# power.net
KiCad netlist of a schematic drawn in Altium Designer
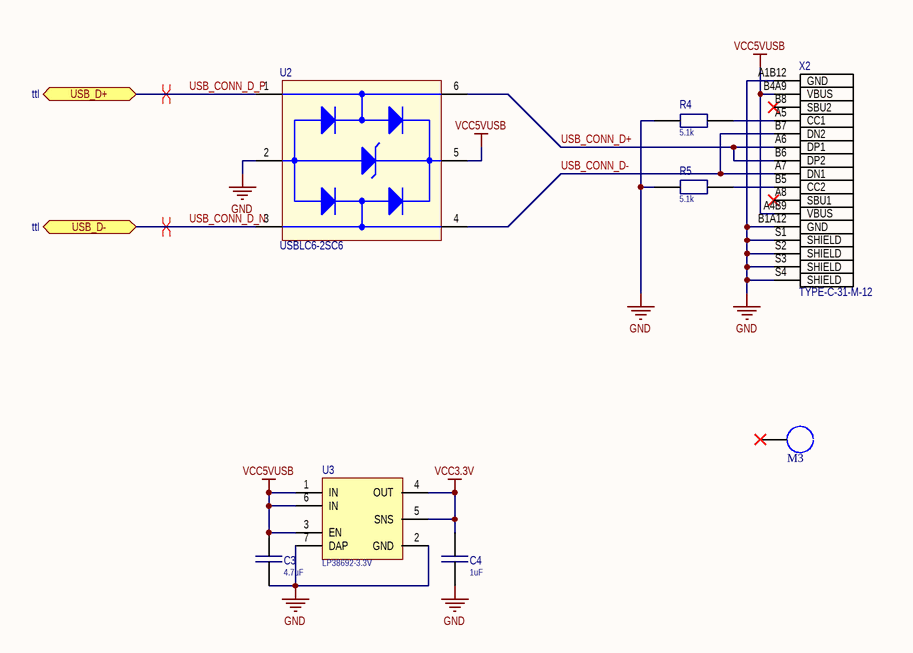
[diagram p0: power.SchDoc]

(export (version "E")
  (design (tool "Eeschema 10.0.6"))
  (components
    (comp (ref "*1") (value "M3") (footprint "M3") (libsource (lib "connectors_socets") (part "M3")))
    (comp (ref "C3")
      (value "4.7uF")
      (footprint "C_0603")
      (description "Capacitor")
      (fields (field (name "PART NUMBER") "CC0603KRX5R6BB475"))
      (libsource (lib "capacitors") (part "CAP_SMD"))
    )
    (comp (ref "C4")
      (value "1uF")
      (footprint "C_0603")
      (description "Capacitor")
      (fields (field (name "PART NUMBER") "CC0603ZRY5V7BB105"))
      (libsource (lib "capacitors") (part "CAP_SMD"))
    )
    (comp (ref "R4")
      (value "5.1k")
      (footprint "R_0603")
      (description "Resistor")
      (fields (field (name "PART NUMBER") "RC0603FR-075K1L"))
      (libsource (lib "resistors") (part "RES_SMD"))
    )
    (comp (ref "R5")
      (value "5.1k")
      (footprint "R_0603")
      (description "Resistor")
      (fields (field (name "PART NUMBER") "RC0603FR-075K1L"))
      (libsource (lib "resistors") (part "RES_SMD"))
    )
    (comp (ref "U2")
      (value "USBLC6-2SC6")
      (footprint "diode:SOT95P280X145-6N")
      (description "17V Clamp 5A (8/20Âµs) Ipp Tvs Diode Surface Mount SOT-23-6")
      (fields (field (name "MF") "STMicroelectronics"))
      (libsource (lib "diode") (part "USBLC6-2SC6"))
    )
    (comp (ref "U3")
      (value "LP38692-3.3V")
      (footprint "WSON-6")
      (description "LP38690, LP38692 1-A LDO CMOS Linear Regulators  Stable with Ceramic Output Capacitors")
      (libsource (lib "AX_Altium_v2.3") (part "LP38692"))
    )
    (comp (ref "X2")
      (value "TYPE-C-31-M-12")
      (footprint "connectors_socets:HRO_TYPE-C-31-M-12")
      (description "USB Connectors 24 Receptacle 1 8.94*7.3mm RoHS")
      (libsource (lib "connectors_socets") (part "TYPE-C-31-M-12"))
    )
  )
  (nets
    (net (code "1") (name "/USB_CONN_D+") (class "Default")
      (node (ref "U2") (pin "6") (pinfunction "I/O1_OUT_6") (pintype "passive"))
      (node (ref "X2") (pin "A6") (pinfunction "DP1_A6") (pintype "passive"))
      (node (ref "X2") (pin "B6") (pinfunction "DP2_B6") (pintype "passive"))
    )
    (net (code "2") (name "/USB_CONN_D-") (class "Default")
      (node (ref "U2") (pin "4") (pinfunction "I/O2_OUT_4") (pintype "passive"))
      (node (ref "X2") (pin "A7") (pinfunction "DN1_A7") (pintype "passive"))
      (node (ref "X2") (pin "B7") (pinfunction "DN2_B7") (pintype "passive"))
    )
    (net (code "3") (name "/USB_CONN_D_N") (class "Default")
      (node (ref "U2") (pin "3") (pinfunction "I/O2_IN_3") (pintype "passive"))
    )
    (net (code "4") (name "/USB_CONN_D_P") (class "Default")
      (node (ref "U2") (pin "1") (pinfunction "I/O1_IN_1") (pintype "passive"))
    )
    (net (code "5") (name "GND") (class "Default")
      (node (ref "C3") (pin "1") (pinfunction "1_1") (pintype "passive"))
      (node (ref "C4") (pin "1") (pinfunction "1_1") (pintype "passive"))
      (node (ref "R4") (pin "1") (pinfunction "1_1") (pintype "passive"))
      (node (ref "R5") (pin "1") (pinfunction "1_1") (pintype "passive"))
      (node (ref "U2") (pin "2") (pinfunction "GND_2") (pintype "passive"))
      (node (ref "U3") (pin "2") (pinfunction "GND_2") (pintype "passive"))
      (node (ref "U3") (pin "7") (pinfunction "DAP_7") (pintype "passive"))
      (node (ref "X2") (pin "A1B12") (pinfunction "GND_A1B12") (pintype "passive"))
      (node (ref "X2") (pin "B1A12") (pinfunction "GND_B1A12") (pintype "passive"))
      (node (ref "X2") (pin "S1") (pinfunction "SHIELD_S1") (pintype "passive"))
      (node (ref "X2") (pin "S2") (pinfunction "SHIELD_S2") (pintype "passive"))
      (node (ref "X2") (pin "S3") (pinfunction "SHIELD_S3") (pintype "passive"))
      (node (ref "X2") (pin "S4") (pinfunction "SHIELD_S4") (pintype "passive"))
    )
    (net (code "6") (name "Net-(X2-CC1)") (class "Default")
      (node (ref "R4") (pin "2") (pinfunction "2_2") (pintype "passive"))
      (node (ref "X2") (pin "A5") (pinfunction "CC1_A5") (pintype "passive"))
    )
    (net (code "7") (name "Net-(X2-CC2)") (class "Default")
      (node (ref "R5") (pin "2") (pinfunction "2_2") (pintype "passive"))
      (node (ref "X2") (pin "B5") (pinfunction "CC2_B5") (pintype "passive"))
    )
    (net (code "8") (name "VCC3.3V") (class "Default")
      (node (ref "C4") (pin "2") (pinfunction "2_2") (pintype "passive"))
      (node (ref "U3") (pin "4") (pinfunction "OUT_4") (pintype "passive"))
      (node (ref "U3") (pin "5") (pinfunction "SNS_5") (pintype "passive"))
    )
    (net (code "9") (name "VCC5VUSB") (class "Default")
      (node (ref "C3") (pin "2") (pinfunction "2_2") (pintype "passive"))
      (node (ref "U2") (pin "5") (pinfunction "VBUS_5") (pintype "passive"))
      (node (ref "U3") (pin "1") (pinfunction "IN_1") (pintype "passive"))
      (node (ref "U3") (pin "3") (pinfunction "EN_3") (pintype "passive"))
      (node (ref "U3") (pin "6") (pinfunction "IN_6") (pintype "passive"))
      (node (ref "X2") (pin "A4B9") (pinfunction "VBUS_A4B9") (pintype "passive"))
      (node (ref "X2") (pin "B4A9") (pinfunction "VBUS_B4A9") (pintype "passive"))
    )
    (net (code "10") (name "unconnected-(*1-Pad1)") (class "Default")
      (node (ref "*1") (pin "1") (pinfunction "1_1") (pintype "passive+no_connect"))
    )
    (net (code "11") (name "unconnected-(X2-SBU1-PadA8)") (class "Default")
      (node (ref "X2") (pin "A8") (pinfunction "SBU1_A8") (pintype "passive+no_connect"))
    )
    (net (code "12") (name "unconnected-(X2-SBU2-PadB8)") (class "Default")
      (node (ref "X2") (pin "B8") (pinfunction "SBU2_B8") (pintype "passive+no_connect"))
    )
  )
)
